# OpAmp_Inverting.net
KiCad netlist of a schematic drawn in Altium Designer
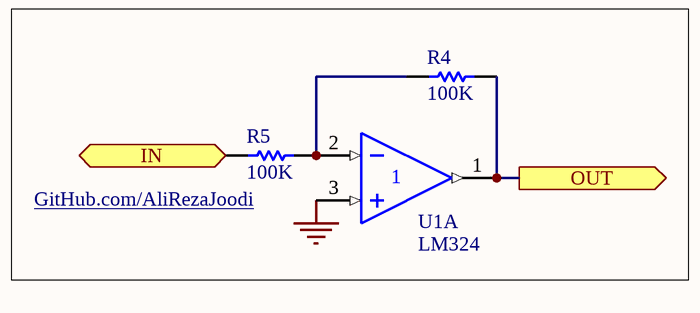
[diagram p0: OpAmp_Inverting.SchDoc]

(export (version "E")
  (design (tool "Eeschema 10.0.6"))
  (components
    (comp (ref "R4")
      (value "100K")
      (footprint "AXIAL-0.4")
      (description "Resistor")
      (fields (field (name "PUBLISHER") "Altium Limited"))
      (libsource (lib "Miscellaneous Devices") (part "Res1"))
    )
    (comp (ref "R5")
      (value "100K")
      (footprint "AXIAL-0.4")
      (description "Resistor")
      (fields (field (name "PUBLISHER") "Altium Limited"))
      (libsource (lib "Miscellaneous Devices") (part "Res1"))
    )
    (comp (ref "U1")
      (value "LM324")
      (footprint "646-06")
      (description "Quad Low-Power Operational Amplifier")
      (fields (field (name "PUBLISHER") "Altium Limited"))
      (libsource (lib "my Libraries") (part "LM324"))
    )
  )
  (nets
    (net (code "1") (name "/IN") (class "Default")
      (node (ref "R5") (pin "2") (pinfunction "2_2") (pintype "passive"))
    )
    (net (code "2") (name "/OUT") (class "Default")
      (node (ref "R4") (pin "2") (pinfunction "2_2") (pintype "passive"))
      (node (ref "U1") (pin "1") (pinfunction "OUT_1") (pintype "output"))
    )
    (net (code "3") (name "GND") (class "Default")
      (node (ref "U1") (pin "3") (pinfunction "IN+_3") (pintype "input"))
    )
    (net (code "4") (name "Net-(U1A-IN-)") (class "Default")
      (node (ref "R4") (pin "1") (pinfunction "1_1") (pintype "passive"))
      (node (ref "R5") (pin "1") (pinfunction "1_1") (pintype "passive"))
      (node (ref "U1") (pin "2") (pinfunction "IN-_2") (pintype "input"))
    )
  )
)
